# Alimentacion.net
KiCad netlist of a schematic drawn in Altium Designer
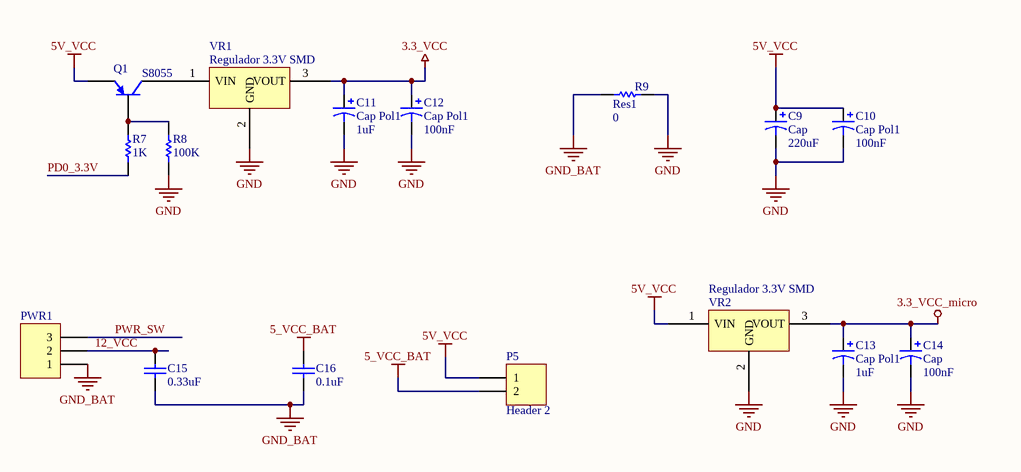
[diagram p0: Alimentacion.SchDoc]

(export (version "E")
  (design (tool "Eeschema 10.0.6"))
  (components
    (comp (ref "C9")
      (value "Cap")
      (footprint "C0805")
      (description "Polarized Capacitor (Radial)")
      (fields (field (name "ALTIUM_VALUE") "220uF") (field (name "PUBLISHER") "Altium Limited"))
      (libsource (lib "Miscellaneous Devices") (part "Cap Pol1"))
    )
    (comp (ref "C10")
      (value "Cap Pol1")
      (footprint "6-0805_L")
      (description "Polarized Capacitor (Radial)")
      (fields (field (name "ALTIUM_VALUE") "100nF") (field (name "PUBLISHER") "Altium Limited"))
      (libsource (lib "Miscellaneous Devices") (part "Cap Pol1"))
    )
    (comp (ref "C11")
      (value "Cap Pol1")
      (footprint "C0805")
      (description "Polarized Capacitor (Radial)")
      (fields (field (name "ALTIUM_VALUE") "1uF") (field (name "PUBLISHER") "Altium Limited"))
      (libsource (lib "Miscellaneous Devices") (part "Cap Pol1"))
    )
    (comp (ref "C12")
      (value "Cap Pol1")
      (footprint "C0805")
      (description "Polarized Capacitor (Radial)")
      (fields (field (name "ALTIUM_VALUE") "100nF") (field (name "PUBLISHER") "Altium Limited"))
      (libsource (lib "Miscellaneous Devices") (part "Cap Pol1"))
    )
    (comp (ref "C13")
      (value "Cap Pol1")
      (footprint "C0805")
      (description "Polarized Capacitor (Radial)")
      (fields (field (name "ALTIUM_VALUE") "1uF") (field (name "PUBLISHER") "Altium Limited"))
      (libsource (lib "Miscellaneous Devices") (part "Cap Pol1"))
    )
    (comp (ref "C14")
      (value "Cap")
      (footprint "6-0805_L")
      (description "Polarized Capacitor (Radial)")
      (fields (field (name "ALTIUM_VALUE") "100nF") (field (name "PUBLISHER") "Altium Limited"))
      (libsource (lib "Miscellaneous Devices") (part "Cap Pol1"))
    )
    (comp (ref "C15")
      (value "0.33uF")
      (footprint "6-0805_L")
      (description "Capacitor")
      (fields (field (name "Comment") "Cap") (field (name "PUBLISHER") "Altium Limited"))
      (libsource (lib "Miscellaneous Devices") (part "Cap"))
    )
    (comp (ref "C16")
      (value "0.1uF")
      (footprint "C0805")
      (description "Capacitor")
      (fields (field (name "Comment") "Cap") (field (name "PUBLISHER") "Altium Limited"))
      (libsource (lib "Miscellaneous Devices") (part "Cap"))
    )
    (comp (ref "P5")
      (value "Header 2")
      (footprint "HDR1X2")
      (description "Header, 2-Pin")
      (fields (field (name "PUBLISHER") "Altium Limited"))
      (libsource (lib "Miscellaneous Connectors") (part "Header 2"))
    )
    (comp (ref "PWR1")
      (value "Header 3")
      (footprint "HDR1X3")
      (description "Header, 3-Pin")
      (fields (field (name "PUBLISHER") "Altium Limited"))
      (libsource (lib "Miscellaneous Connectors") (part "Header 3"))
    )
    (comp (ref "Q1")
      (value "S8055")
      (footprint "SOT23-3")
      (description "PNP SMD General Purpose Amplifier")
      (fields (field (name "PUBLISHER") "Altium Limited"))
      (libsource (lib "Libreria General") (part "S8055"))
    )
    (comp (ref "R7")
      (value "1K")
      (footprint "C0805")
      (description "Resistor")
      (fields (field (name "Comment") "Res1") (field (name "PUBLISHER") "Altium Limited"))
      (libsource (lib "Miscellaneous Devices") (part "Res1"))
    )
    (comp (ref "R8")
      (value "100K")
      (footprint "C0805")
      (description "Resistor")
      (fields (field (name "Comment") "Res1") (field (name "PUBLISHER") "Altium Limited"))
      (libsource (lib "Miscellaneous Devices") (part "Res1"))
    )
    (comp (ref "R9")
      (value "Res1")
      (footprint "C0805")
      (description "Resistor")
      (fields (field (name "ALTIUM_VALUE") "0") (field (name "PUBLISHER") "Altium Limited"))
      (libsource (lib "Miscellaneous Devices") (part "Res1"))
    )
    (comp (ref "VR1")
      (value "Regulador 3.3V SMD")
      (footprint "SOT223")
      (description "AMS1117")
      (libsource (lib "Libreria General") (part "Regulador 3.3V SMD"))
    )
    (comp (ref "VR2")
      (value "Regulador 3.3V SMD")
      (footprint "SOT223")
      (description "AMS1117")
      (libsource (lib "Libreria General") (part "Regulador 3.3V SMD"))
    )
  )
  (nets
    (net (code "1") (name "/12_VCC") (class "Default")
      (node (ref "C15") (pin "2") (pinfunction "2_2") (pintype "passive"))
      (node (ref "PWR1") (pin "2") (pinfunction "2_2") (pintype "passive"))
    )
    (net (code "2") (name "/PD0_3.3V") (class "Default")
      (node (ref "R7") (pin "1") (pinfunction "1_1") (pintype "passive"))
    )
    (net (code "3") (name "/PWR_SW") (class "Default")
      (node (ref "PWR1") (pin "3") (pinfunction "3_3") (pintype "passive"))
    )
    (net (code "4") (name "3.3_VCC") (class "Default")
      (node (ref "C11") (pin "1") (pinfunction "1_1") (pintype "passive"))
      (node (ref "C12") (pin "1") (pinfunction "1_1") (pintype "passive"))
      (node (ref "VR1") (pin "3") (pinfunction "VOUT_3") (pintype "passive"))
    )
    (net (code "5") (name "3.3_VCC_micro") (class "Default")
      (node (ref "C13") (pin "1") (pinfunction "1_1") (pintype "passive"))
      (node (ref "C14") (pin "1") (pinfunction "1_1") (pintype "passive"))
      (node (ref "VR2") (pin "3") (pinfunction "VOUT_3") (pintype "passive"))
    )
    (net (code "6") (name "5V_VCC") (class "Default")
      (node (ref "C10") (pin "1") (pinfunction "1_1") (pintype "passive"))
      (node (ref "C9") (pin "1") (pinfunction "1_1") (pintype "passive"))
      (node (ref "P5") (pin "1") (pinfunction "1_1") (pintype "passive"))
      (node (ref "Q1") (pin "2") (pinfunction "E_2") (pintype "passive"))
      (node (ref "VR2") (pin "1") (pinfunction "VIN_1") (pintype "passive"))
    )
    (net (code "7") (name "5_VCC_BAT") (class "Default")
      (node (ref "C16") (pin "2") (pinfunction "2_2") (pintype "passive"))
      (node (ref "P5") (pin "2") (pinfunction "2_2") (pintype "passive"))
    )
    (net (code "8") (name "GND") (class "Default")
      (node (ref "C10") (pin "2") (pinfunction "2_2") (pintype "passive"))
      (node (ref "C11") (pin "2") (pinfunction "2_2") (pintype "passive"))
      (node (ref "C12") (pin "2") (pinfunction "2_2") (pintype "passive"))
      (node (ref "C13") (pin "2") (pinfunction "2_2") (pintype "passive"))
      (node (ref "C14") (pin "2") (pinfunction "2_2") (pintype "passive"))
      (node (ref "C9") (pin "2") (pinfunction "2_2") (pintype "passive"))
      (node (ref "R8") (pin "1") (pinfunction "1_1") (pintype "passive"))
      (node (ref "R9") (pin "2") (pinfunction "2_2") (pintype "passive"))
      (node (ref "VR1") (pin "2") (pinfunction "GND_2") (pintype "passive"))
      (node (ref "VR2") (pin "2") (pinfunction "GND_2") (pintype "passive"))
    )
    (net (code "9") (name "GND_BAT") (class "Default")
      (node (ref "C15") (pin "1") (pinfunction "1_1") (pintype "passive"))
      (node (ref "C16") (pin "1") (pinfunction "1_1") (pintype "passive"))
      (node (ref "PWR1") (pin "1") (pinfunction "1_1") (pintype "passive"))
      (node (ref "R9") (pin "1") (pinfunction "1_1") (pintype "passive"))
    )
    (net (code "10") (name "Net-(Q1-B)") (class "Default")
      (node (ref "Q1") (pin "1") (pinfunction "B_1") (pintype "passive"))
      (node (ref "R7") (pin "2") (pinfunction "2_2") (pintype "passive"))
      (node (ref "R8") (pin "2") (pinfunction "2_2") (pintype "passive"))
    )
    (net (code "11") (name "Net-(Q1-C)") (class "Default")
      (node (ref "Q1") (pin "3") (pinfunction "C_3") (pintype "passive"))
      (node (ref "VR1") (pin "1") (pinfunction "VIN_1") (pintype "passive"))
    )
  )
)
